# Inverter_Main.net
KiCad netlist of a schematic drawn in Altium Designer
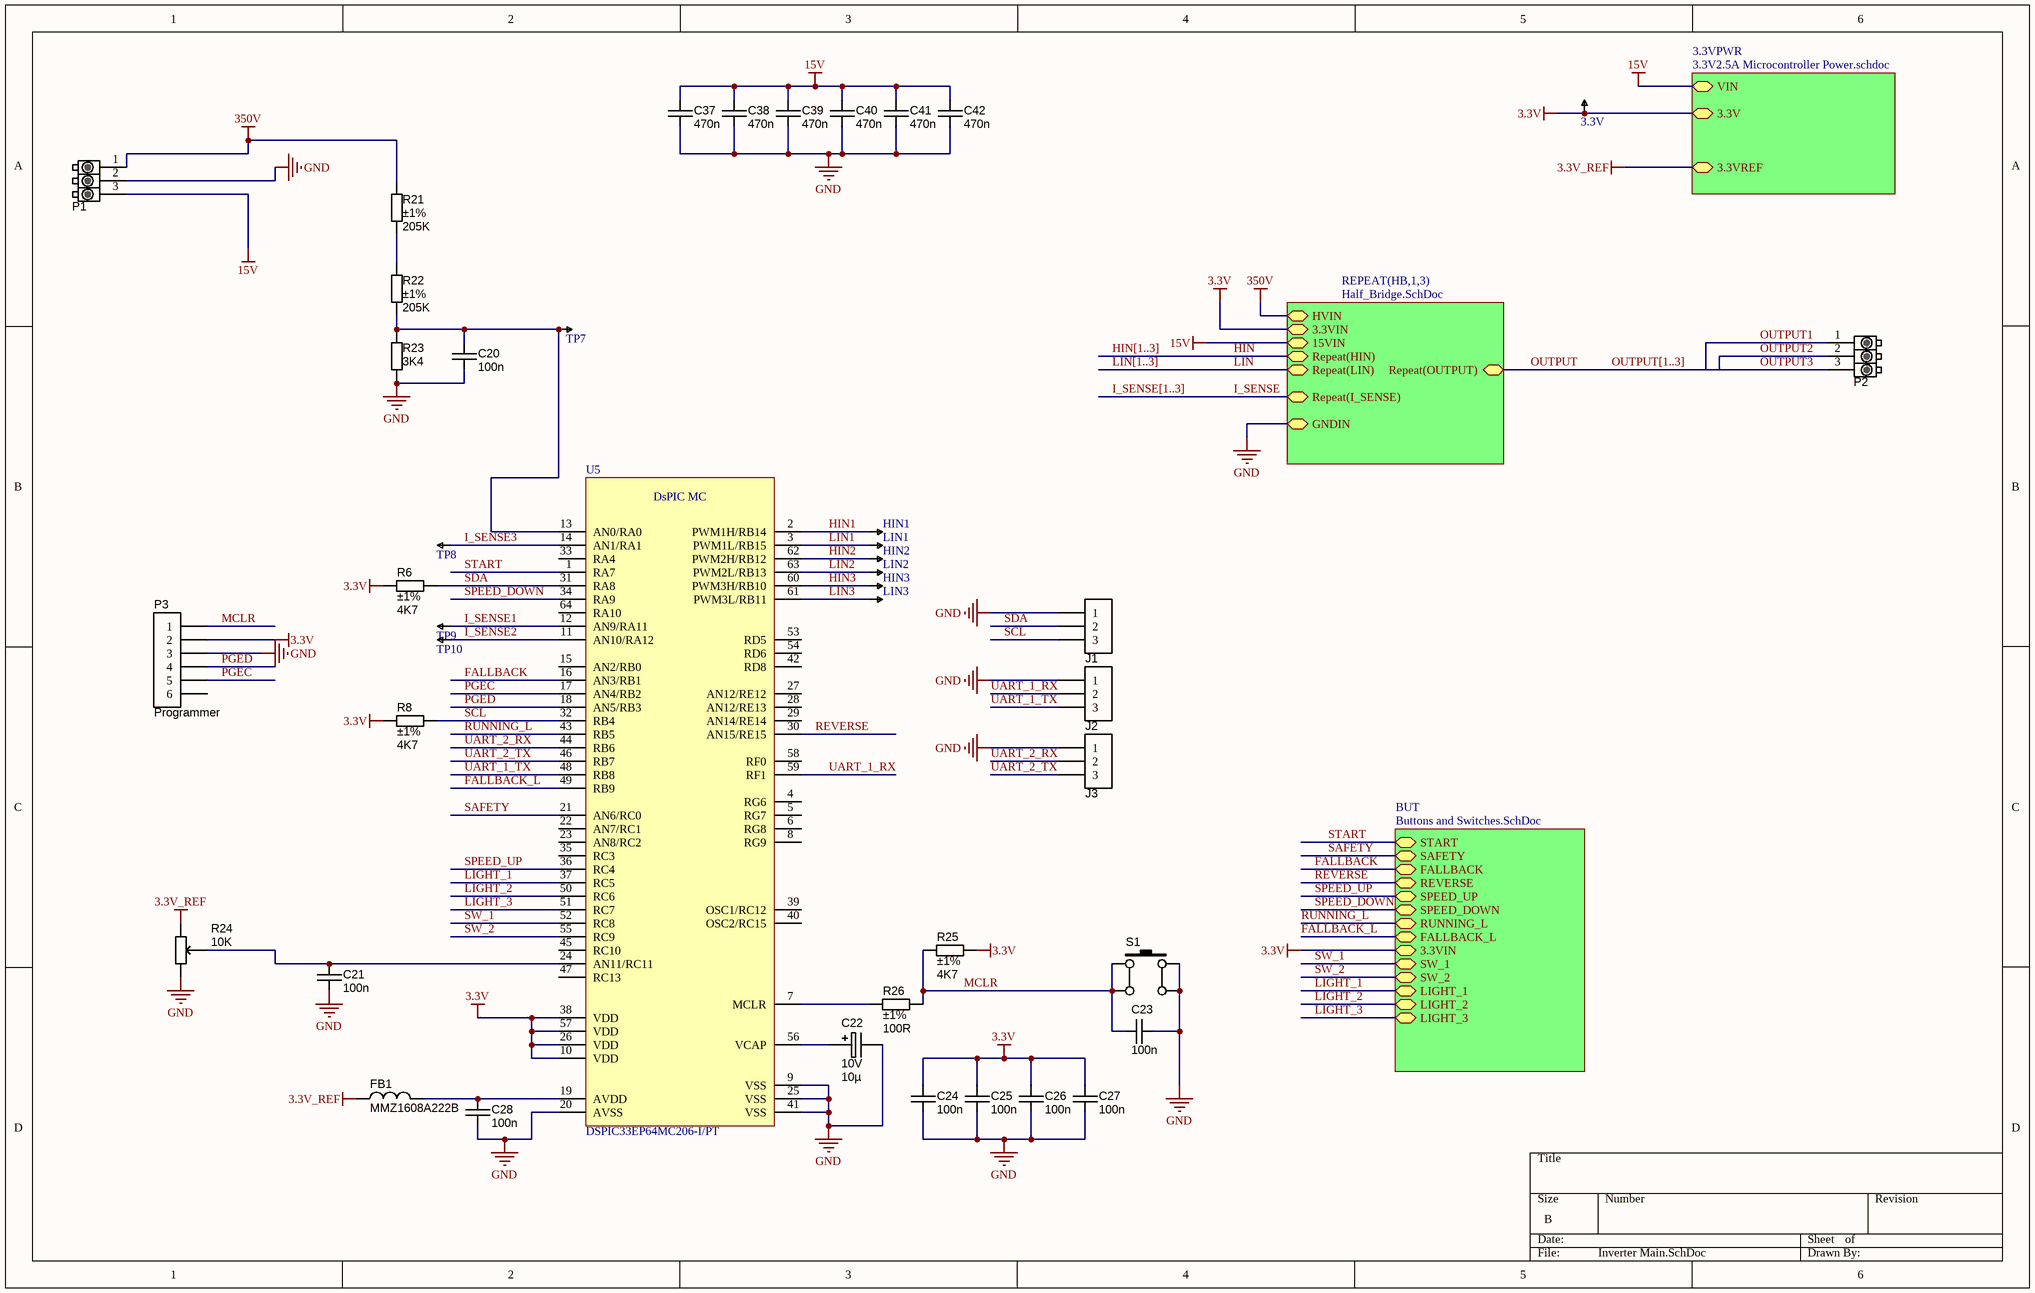
[diagram p0: Inverter Main.SchDoc]

(export (version "E")
  (design (tool "Eeschema 10.0.6"))
  (components
    (comp (ref "3.3V")
      (value "TESTPOINT SMD 1206")
      (footprint "1206 Test Point")
      (fields
        (field (name "MANUFACTURER") "TE Connectivity AMP Connectors")
        (field (name "MANUFACTURER PART NUMBER") "RCS-0C")
      )
      (libsource (lib "PBL - Test Points") (part "TESTPOINT SMD 1206"))
    )
    (comp (ref "C20")
      (value "100n")
      (footprint "CAPC1608X90N")
      (description "Capacitor SMD Cer 100nF 10% 50V X7R 0603")
      (fields
        (field (name "TOLERANCE") "±10%")
        (field (name "MANUFACTURER") "Murata Electronics North America")
      )
      (libsource (lib "PBL - Capacitors") (part "CAPC_100n_0603_X7R_50V_10%"))
    )
    (comp (ref "C21")
      (value "100n")
      (footprint "CAPC1608X90N")
      (description "Capacitor SMD Cer 100nF 10% 50V X7R 0603")
      (fields
        (field (name "TOLERANCE") "±10%")
        (field (name "MANUFACTURER") "Murata Electronics North America")
      )
      (libsource (lib "PBL - Capacitors") (part "CAPC_100n_0603_X7R_50V_10%"))
    )
    (comp (ref "C22")
      (value "10µ")
      (footprint "CAPMP2012X150USR")
      (description "Capacitor SMD Tantalum 10uF 20% 10V 0805")
      (fields (field (name "TOLERANCE") "±20%") (field (name "RATINGS") "10V"))
      (libsource (lib "PBL - Capacitors") (part "CAPT_10u_0805_10V"))
    )
    (comp (ref "C23")
      (value "100n")
      (footprint "CAPC1608X90N")
      (description "Capacitor SMD Cer 100nF 10% 50V X7R 0603")
      (fields
        (field (name "TOLERANCE") "±10%")
        (field (name "MANUFACTURER") "Murata Electronics North America")
      )
      (libsource (lib "PBL - Capacitors") (part "CAPC_100n_0603_X7R_50V_10%"))
    )
    (comp (ref "C24")
      (value "100n")
      (footprint "CAPC1608X90N")
      (description "Capacitor SMD Cer 100nF 10% 50V X7R 0603")
      (fields
        (field (name "TOLERANCE") "±10%")
        (field (name "MANUFACTURER") "Murata Electronics North America")
      )
      (libsource (lib "PBL - Capacitors") (part "CAPC_100n_0603_X7R_50V_10%"))
    )
    (comp (ref "C25")
      (value "100n")
      (footprint "CAPC1608X90N")
      (description "Capacitor SMD Cer 100nF 10% 50V X7R 0603")
      (fields
        (field (name "TOLERANCE") "±10%")
        (field (name "MANUFACTURER") "Murata Electronics North America")
      )
      (libsource (lib "PBL - Capacitors") (part "CAPC_100n_0603_X7R_50V_10%"))
    )
    (comp (ref "C26")
      (value "100n")
      (footprint "CAPC1608X90N")
      (description "Capacitor SMD Cer 100nF 10% 50V X7R 0603")
      (fields
        (field (name "TOLERANCE") "±10%")
        (field (name "MANUFACTURER") "Murata Electronics North America")
      )
      (libsource (lib "PBL - Capacitors") (part "CAPC_100n_0603_X7R_50V_10%"))
    )
    (comp (ref "C27")
      (value "100n")
      (footprint "CAPC1608X90N")
      (description "Capacitor SMD Cer 100nF 10% 50V X7R 0603")
      (fields
        (field (name "TOLERANCE") "±10%")
        (field (name "MANUFACTURER") "Murata Electronics North America")
      )
      (libsource (lib "PBL - Capacitors") (part "CAPC_100n_0603_X7R_50V_10%"))
    )
    (comp (ref "C28")
      (value "100n")
      (footprint "CAPC1608X90N")
      (description "Capacitor SMD Cer 100nF 10% 50V X7R 0603")
      (fields
        (field (name "TOLERANCE") "±10%")
        (field (name "MANUFACTURER") "Murata Electronics North America")
      )
      (libsource (lib "PBL - Capacitors") (part "CAPC_100n_0603_X7R_50V_10%"))
    )
    (comp (ref "C37")
      (value "470n")
      (footprint "CAPC2012X135N")
      (description "0.47µF ±10% 50V Ceramic Capacitor X7R 0805 (2012 Metric)")
      (fields
        (field (name "MANUFACTURER") "Murata Electronics North America")
        (field (name "TOLERANCE") "±10%")
      )
      (libsource (lib "PBL - Capacitors") (part "CAPC_470n_0805_X7R_50V_10%"))
    )
    (comp (ref "C38")
      (value "470n")
      (footprint "CAPC2012X135N")
      (description "0.47µF ±10% 50V Ceramic Capacitor X7R 0805 (2012 Metric)")
      (fields
        (field (name "MANUFACTURER") "Murata Electronics North America")
        (field (name "TOLERANCE") "±10%")
      )
      (libsource (lib "PBL - Capacitors") (part "CAPC_470n_0805_X7R_50V_10%"))
    )
    (comp (ref "C39")
      (value "470n")
      (footprint "CAPC2012X135N")
      (description "0.47µF ±10% 50V Ceramic Capacitor X7R 0805 (2012 Metric)")
      (fields
        (field (name "MANUFACTURER") "Murata Electronics North America")
        (field (name "TOLERANCE") "±10%")
      )
      (libsource (lib "PBL - Capacitors") (part "CAPC_470n_0805_X7R_50V_10%"))
    )
    (comp (ref "C40")
      (value "470n")
      (footprint "CAPC2012X135N")
      (description "0.47µF ±10% 50V Ceramic Capacitor X7R 0805 (2012 Metric)")
      (fields
        (field (name "MANUFACTURER") "Murata Electronics North America")
        (field (name "TOLERANCE") "±10%")
      )
      (libsource (lib "PBL - Capacitors") (part "CAPC_470n_0805_X7R_50V_10%"))
    )
    (comp (ref "C41")
      (value "470n")
      (footprint "CAPC2012X135N")
      (description "0.47µF ±10% 50V Ceramic Capacitor X7R 0805 (2012 Metric)")
      (fields
        (field (name "MANUFACTURER") "Murata Electronics North America")
        (field (name "TOLERANCE") "±10%")
      )
      (libsource (lib "PBL - Capacitors") (part "CAPC_470n_0805_X7R_50V_10%"))
    )
    (comp (ref "C42")
      (value "470n")
      (footprint "CAPC2012X135N")
      (description "0.47µF ±10% 50V Ceramic Capacitor X7R 0805 (2012 Metric)")
      (fields
        (field (name "MANUFACTURER") "Murata Electronics North America")
        (field (name "TOLERANCE") "±10%")
      )
      (libsource (lib "PBL - Capacitors") (part "CAPC_470n_0805_X7R_50V_10%"))
    )
    (comp (ref "FB1")
      (value "2K2 @ 100 MHz")
      (footprint "FBC1608X95N")
      (description "Ferrite bead 2.2K Ohm at 100 MHz 200mA 0603 SMD")
      (fields (field (name "MANUFACTURER PART NUMBER 1") "MMZ1608A222B"))
      (libsource (lib "PBL - Inductors") (part "FERRITE_2K2-100MHz_0603"))
    )
    (comp (ref "HIN1")
      (value "TESTPOINT SMD 1206")
      (footprint "1206 Test Point")
      (fields
        (field (name "MANUFACTURER") "TE Connectivity AMP Connectors")
        (field (name "MANUFACTURER PART NUMBER") "RCS-0C")
      )
      (libsource (lib "PBL - Test Points") (part "TESTPOINT SMD 1206"))
    )
    (comp (ref "HIN2")
      (value "TESTPOINT SMD 1206")
      (footprint "1206 Test Point")
      (fields
        (field (name "MANUFACTURER") "TE Connectivity AMP Connectors")
        (field (name "MANUFACTURER PART NUMBER") "RCS-0C")
      )
      (libsource (lib "PBL - Test Points") (part "TESTPOINT SMD 1206"))
    )
    (comp (ref "HIN3")
      (value "TESTPOINT SMD 1206")
      (footprint "1206 Test Point")
      (fields
        (field (name "MANUFACTURER") "TE Connectivity AMP Connectors")
        (field (name "MANUFACTURER PART NUMBER") "RCS-0C")
      )
      (libsource (lib "PBL - Test Points") (part "TESTPOINT SMD 1206"))
    )
    (comp (ref "J1")
      (value "JST_PH_B3B")
      (footprint "JST_PH_3_B3B")
      (description "2mm Pitch")
      (libsource (lib "PBL - Connectors") (part "JST_PH_B3B"))
    )
    (comp (ref "J2")
      (value "JST_PH_B3B")
      (footprint "JST_PH_3_B3B")
      (description "2mm Pitch")
      (libsource (lib "PBL - Connectors") (part "JST_PH_B3B"))
    )
    (comp (ref "J3")
      (value "JST_PH_B3B")
      (footprint "JST_PH_3_B3B")
      (description "2mm Pitch")
      (libsource (lib "PBL - Connectors") (part "JST_PH_B3B"))
    )
    (comp (ref "LIN1")
      (value "TESTPOINT SMD 1206")
      (footprint "1206 Test Point")
      (fields
        (field (name "MANUFACTURER") "TE Connectivity AMP Connectors")
        (field (name "MANUFACTURER PART NUMBER") "RCS-0C")
      )
      (libsource (lib "PBL - Test Points") (part "TESTPOINT SMD 1206"))
    )
    (comp (ref "LIN2")
      (value "TESTPOINT SMD 1206")
      (footprint "1206 Test Point")
      (fields
        (field (name "MANUFACTURER") "TE Connectivity AMP Connectors")
        (field (name "MANUFACTURER PART NUMBER") "RCS-0C")
      )
      (libsource (lib "PBL - Test Points") (part "TESTPOINT SMD 1206"))
    )
    (comp (ref "LIN3")
      (value "TESTPOINT SMD 1206")
      (footprint "1206 Test Point")
      (fields
        (field (name "MANUFACTURER") "TE Connectivity AMP Connectors")
        (field (name "MANUFACTURER PART NUMBER") "RCS-0C")
      )
      (libsource (lib "PBL - Test Points") (part "TESTPOINT SMD 1206"))
    )
    (comp (ref "P1")
      (value "3P_TERM BLOCK 796739-3")
      (footprint "TE 796739-3 3 Screw Terminal")
      (description "3 Position Wire to Board Terminal Block Horizontal with Board 0.375\" (9.53mm) Through Hole")
      (fields (field (name "MANUFACTURER") "TE Connectivity AMP Connectors") (field (name "VOLTAGE") "600V"))
      (libsource (lib "PBL - Connectors") (part "3P_TERM BLOCK 796739-3"))
    )
    (comp (ref "P2")
      (value "3P_TERM BLOCK 796739-3")
      (footprint "TE 796739-3 3 Screw Terminal")
      (description "3 Position Wire to Board Terminal Block Horizontal with Board 0.375\" (9.53mm) Through Hole")
      (fields (field (name "MANUFACTURER") "TE Connectivity AMP Connectors") (field (name "VOLTAGE") "600V"))
      (libsource (lib "") (part "3P_TERM BLOCK 796739-3_1"))
    )
    (comp (ref "P3")
      (value "Programmer")
      (footprint "HDR1X6")
      (description "Header, 6-pin")
      (libsource (lib "PBL - Connectors") (part "Header6P"))
    )
    (comp (ref "R6")
      (value "4K7")
      (footprint "RESC1608X55N")
      (description "Resistor SMD chip 4.7K Ohm 0.1W 1% 0603")
      (fields
        (field (name "MANUFACTURER") "Yageo")
        (field (name "MANUFACTURER PART NUMBER") "RC0603FR-074K7L")
        (field (name "TOLERANCE") "±1%")
      )
      (libsource (lib "PBL - Resistors") (part "RES_4K7_0603_1%"))
    )
    (comp (ref "R8")
      (value "4K7")
      (footprint "RESC1608X55N")
      (description "Resistor SMD chip 4.7K Ohm 0.1W 1% 0603")
      (fields
        (field (name "MANUFACTURER") "Yageo")
        (field (name "MANUFACTURER PART NUMBER") "RC0603FR-074K7L")
        (field (name "TOLERANCE") "±1%")
      )
      (libsource (lib "PBL - Resistors") (part "RES_4K7_0603_1%"))
    )
    (comp (ref "R21")
      (value "205K")
      (footprint "RESC2012X70N")
      (description "Resistor SMD chip 205k Ohm 0.125W 1% 0805")
      (fields (field (name "TOLERANCE") "±1%") (field (name "Comment") "Thick Film"))
      (libsource (lib "PBL - Resistors") (part "RES_205K_0805_1%"))
    )
    (comp (ref "R22")
      (value "205K")
      (footprint "RESC2012X70N")
      (description "Resistor SMD chip 205k Ohm 0.125W 1% 0805")
      (fields (field (name "TOLERANCE") "±1%") (field (name "Comment") "Thick Film"))
      (libsource (lib "PBL - Resistors") (part "RES_205K_0805_1%"))
    )
    (comp (ref "R23")
      (value "3K4")
      (footprint "RESC1608X55N")
      (description "Resistor SMD chip 3.4k Ohm 0.1W 1% 0603")
      (fields
        (field (name "TOLERANCE") "±1%")
        (field (name "MANUFACTURER") "Panasonic Electronic Components")
      )
      (libsource (lib "PBL - Resistors") (part "RES_3K4_0603_1%"))
    )
    (comp (ref "R24")
      (value "10K")
      (footprint "POT_PDB12_BOURNS")
      (description "10k Ohm 1 Gang Linear Through Hole Potentiometer None 1 Turn Carbon 0.08W PC Pins, Board Locks")
      (fields (field (name "MANUFACTURER") "Bourns Inc.") (field (name "TOLERANCE") "±20%"))
      (libsource (lib "PBL - Resistors") (part "RES_POT_10K_THT_PDB12-H4251-103BF"))
    )
    (comp (ref "R25")
      (value "4K7")
      (footprint "RESC1608X55N")
      (description "Resistor SMD chip 4.7K Ohm 0.1W 1% 0603")
      (fields
        (field (name "MANUFACTURER") "Yageo")
        (field (name "MANUFACTURER PART NUMBER") "RC0603FR-074K7L")
        (field (name "TOLERANCE") "±1%")
      )
      (libsource (lib "PBL - Resistors") (part "RES_4K7_0603_1%"))
    )
    (comp (ref "R26")
      (value "100R")
      (footprint "RESC1608X55N")
      (description "Resistor SMD chip 100 Ohm 0.1W 1% 0603")
      (fields (field (name "TOLERANCE") "±1%") (field (name "Comment") "Thick Film"))
      (libsource (lib "PBL - Resistors") (part "RES_100R_0603_1%"))
    )
    (comp (ref "S1")
      (value "TL3301AF160QJ")
      (footprint "SWITCH_TACT_JLEAD_6mm")
      (description "TACT_SWITCH 6x6 Jlead TL3301AF160QJ")
      (fields (field (name "MANUFACTURER") "E-Switch"))
      (libsource (lib "PBL - Switches") (part "TACT_SWITCH 6x6 JLEAD TL3301AF160QJ"))
    )
    (comp (ref "TP7")
      (value "TESTPOINT SMD 1206")
      (footprint "1206 Test Point")
      (fields
        (field (name "MANUFACTURER") "TE Connectivity AMP Connectors")
        (field (name "MANUFACTURER PART NUMBER") "RCS-0C")
      )
      (libsource (lib "PBL - Test Points") (part "TESTPOINT SMD 1206"))
    )
    (comp (ref "TP8")
      (value "TESTPOINT SMD 1206")
      (footprint "1206 Test Point")
      (fields
        (field (name "MANUFACTURER") "TE Connectivity AMP Connectors")
        (field (name "MANUFACTURER PART NUMBER") "RCS-0C")
      )
      (libsource (lib "PBL - Test Points") (part "TESTPOINT SMD 1206"))
    )
    (comp (ref "TP9")
      (value "TESTPOINT SMD 1206")
      (footprint "1206 Test Point")
      (fields
        (field (name "MANUFACTURER") "TE Connectivity AMP Connectors")
        (field (name "MANUFACTURER PART NUMBER") "RCS-0C")
      )
      (libsource (lib "PBL - Test Points") (part "TESTPOINT SMD 1206"))
    )
    (comp (ref "TP10")
      (value "TESTPOINT SMD 1206")
      (footprint "1206 Test Point")
      (fields
        (field (name "MANUFACTURER") "TE Connectivity AMP Connectors")
        (field (name "MANUFACTURER PART NUMBER") "RCS-0C")
      )
      (libsource (lib "PBL - Test Points") (part "TESTPOINT SMD 1206"))
    )
    (comp (ref "U5")
      (value "uC_dsPIC33EP64MC206")
      (footprint "LQFP50P1200X1200X160-64")
      (description "DSPIC33EP64MC206-I/PT")
      (fields
        (field (name "MANUFACTURER") "Microchip Technology")
        (field (name "MANUFACTURER PART NUMBER") "DSPIC33EP64MC206-I/PT")
      )
      (libsource (lib "PBL - Integrated Circuits") (part "uC_dsPIC33EP64MC206"))
    )
  )
  (nets
    (net (code "1") (name "/FALLBACK") (class "Default")
      (node (ref "U5") (pin "16") (pinfunction "AN3/RB1_16") (pintype "passive"))
    )
    (net (code "2") (name "/FALLBACK_L") (class "Default")
      (node (ref "U5") (pin "49") (pinfunction "RB9_49") (pintype "passive"))
    )
    (net (code "4") (name "/HIN1") (class "Default")
      (node (ref "HIN1") (pin "1") (pintype "passive"))
      (node (ref "U5") (pin "2") (pinfunction "PWM1H/RB14_2") (pintype "passive"))
    )
    (net (code "5") (name "/HIN2") (class "Default")
      (node (ref "HIN2") (pin "1") (pintype "passive"))
      (node (ref "U5") (pin "62") (pinfunction "PWM2H/RB12_62") (pintype "passive"))
    )
    (net (code "6") (name "/HIN3") (class "Default")
      (node (ref "HIN3") (pin "1") (pintype "passive"))
      (node (ref "U5") (pin "60") (pinfunction "PWM3H/RB10_60") (pintype "passive"))
    )
    (net (code "9") (name "/I_SENSE1") (class "Default")
      (node (ref "TP9") (pin "1") (pintype "passive"))
      (node (ref "U5") (pin "12") (pinfunction "AN9/RA11_12") (pintype "passive"))
    )
    (net (code "10") (name "/I_SENSE2") (class "Default")
      (node (ref "TP10") (pin "1") (pintype "passive"))
      (node (ref "U5") (pin "11") (pinfunction "AN10/RA12_11") (pintype "passive"))
    )
    (net (code "11") (name "/I_SENSE3") (class "Default")
      (node (ref "TP8") (pin "1") (pintype "passive"))
      (node (ref "U5") (pin "14") (pinfunction "AN1/RA1_14") (pintype "passive"))
    )
    (net (code "13") (name "/LIGHT_1") (class "Default")
      (node (ref "U5") (pin "37") (pinfunction "RC5_37") (pintype "passive"))
    )
    (net (code "14") (name "/LIGHT_2") (class "Default")
      (node (ref "U5") (pin "50") (pinfunction "RC6_50") (pintype "passive"))
    )
    (net (code "15") (name "/LIGHT_3") (class "Default")
      (node (ref "U5") (pin "51") (pinfunction "RC7_51") (pintype "passive"))
    )
    (net (code "17") (name "/LIN1") (class "Default")
      (node (ref "LIN1") (pin "1") (pintype "passive"))
      (node (ref "U5") (pin "3") (pinfunction "PWM1L/RB15_3") (pintype "passive"))
    )
    (net (code "18") (name "/LIN2") (class "Default")
      (node (ref "LIN2") (pin "1") (pintype "passive"))
      (node (ref "U5") (pin "63") (pinfunction "PWM2L/RB13_63") (pintype "passive"))
    )
    (net (code "19") (name "/LIN3") (class "Default")
      (node (ref "LIN3") (pin "1") (pintype "passive"))
      (node (ref "U5") (pin "61") (pinfunction "PWM3L/RB11_61") (pintype "passive"))
    )
    (net (code "21") (name "/MCLR") (class "Default")
      (node (ref "C23") (pin "1") (pintype "passive"))
      (node (ref "P3") (pin "1") (pinfunction "1_1") (pintype "passive"))
      (node (ref "R25") (pin "1") (pinfunction "1_1") (pintype "passive"))
      (node (ref "R26") (pin "2") (pinfunction "2_2") (pintype "passive"))
      (node (ref "S1") (pin "1") (pintype "passive"))
      (node (ref "S1") (pin "2") (pintype "passive"))
    )
    (net (code "23") (name "/OUTPUT1") (class "Default")
      (node (ref "P2") (pin "1") (pinfunction "1_1") (pintype "passive"))
    )
    (net (code "24") (name "/OUTPUT2") (class "Default")
      (node (ref "P2") (pin "2") (pinfunction "2_2") (pintype "passive"))
    )
    (net (code "25") (name "/OUTPUT3") (class "Default")
      (node (ref "P2") (pin "3") (pinfunction "3_3") (pintype "passive"))
    )
    (net (code "27") (name "/PGEC") (class "Default")
      (node (ref "P3") (pin "5") (pinfunction "5_5") (pintype "passive"))
      (node (ref "U5") (pin "17") (pinfunction "AN4/RB2_17") (pintype "passive"))
    )
    (net (code "28") (name "/PGED") (class "Default")
      (node (ref "P3") (pin "4") (pinfunction "4_4") (pintype "passive"))
      (node (ref "U5") (pin "18") (pinfunction "AN5/RB3_18") (pintype "passive"))
    )
    (net (code "29") (name "/REVERSE") (class "Default")
      (node (ref "U5") (pin "30") (pinfunction "AN15/RE15_30") (pintype "passive"))
    )
    (net (code "30") (name "/RUNNING_L") (class "Default")
      (node (ref "U5") (pin "43") (pinfunction "RB5_43") (pintype "passive"))
    )
    (net (code "31") (name "/SAFETY") (class "Default")
      (node (ref "U5") (pin "21") (pinfunction "AN6/RC0_21") (pintype "passive"))
    )
    (net (code "32") (name "/SCL") (class "Default")
      (node (ref "J1") (pin "3") (pinfunction "3_3") (pintype "passive"))
      (node (ref "R8") (pin "2") (pinfunction "2_2") (pintype "passive"))
      (node (ref "U5") (pin "32") (pinfunction "RB4_32") (pintype "passive"))
    )
    (net (code "33") (name "/SDA") (class "Default")
      (node (ref "J1") (pin "2") (pinfunction "2_2") (pintype "passive"))
      (node (ref "R6") (pin "2") (pinfunction "2_2") (pintype "passive"))
      (node (ref "U5") (pin "31") (pinfunction "RA8_31") (pintype "passive"))
    )
    (net (code "34") (name "/SPEED_DOWN") (class "Default")
      (node (ref "U5") (pin "34") (pinfunction "RA9_34") (pintype "passive"))
    )
    (net (code "35") (name "/SPEED_UP") (class "Default")
      (node (ref "U5") (pin "36") (pinfunction "RC4_36") (pintype "passive"))
    )
    (net (code "36") (name "/START") (class "Default")
      (node (ref "U5") (pin "1") (pinfunction "RA7_1") (pintype "passive"))
    )
    (net (code "37") (name "/SW_1") (class "Default")
      (node (ref "U5") (pin "52") (pinfunction "RC8_52") (pintype "passive"))
    )
    (net (code "38") (name "/SW_2") (class "Default")
      (node (ref "U5") (pin "55") (pinfunction "RC9_55") (pintype "passive"))
    )
    (net (code "39") (name "/UART_1_RX") (class "Default")
      (node (ref "J2") (pin "2") (pinfunction "2_2") (pintype "passive"))
      (node (ref "U5") (pin "59") (pinfunction "RF1_59") (pintype "passive"))
    )
    (net (code "40") (name "/UART_1_TX") (class "Default")
      (node (ref "J2") (pin "3") (pinfunction "3_3") (pintype "passive"))
      (node (ref "U5") (pin "48") (pinfunction "RB8_48") (pintype "passive"))
    )
    (net (code "41") (name "/UART_2_RX") (class "Default")
      (node (ref "J3") (pin "2") (pinfunction "2_2") (pintype "passive"))
      (node (ref "U5") (pin "44") (pinfunction "RB6_44") (pintype "passive"))
    )
    (net (code "42") (name "/UART_2_TX") (class "Default")
      (node (ref "J3") (pin "3") (pinfunction "3_3") (pintype "passive"))
      (node (ref "U5") (pin "46") (pinfunction "RB7_46") (pintype "passive"))
    )
    (net (code "43") (name "3.3V") (class "Default")
      (node (ref "3.3V") (pin "1") (pintype "passive"))
      (node (ref "C24") (pin "1") (pintype "passive"))
      (node (ref "C25") (pin "1") (pintype "passive"))
      (node (ref "C26") (pin "1") (pintype "passive"))
      (node (ref "C27") (pin "1") (pintype "passive"))
      (node (ref "P3") (pin "2") (pinfunction "2_2") (pintype "passive"))
      (node (ref "R25") (pin "2") (pinfunction "2_2") (pintype "passive"))
      (node (ref "R6") (pin "1") (pinfunction "1_1") (pintype "passive"))
      (node (ref "R8") (pin "1") (pinfunction "1_1") (pintype "passive"))
      (node (ref "U5") (pin "10") (pinfunction "VDD_10") (pintype "passive"))
      (node (ref "U5") (pin "26") (pinfunction "VDD_26") (pintype "passive"))
      (node (ref "U5") (pin "38") (pinfunction "VDD_38") (pintype "passive"))
      (node (ref "U5") (pin "57") (pinfunction "VDD_57") (pintype "passive"))
    )
    (net (code "44") (name "3.3V_REF") (class "Default")
      (node (ref "FB1") (pin "1") (pinfunction "1_1") (pintype "passive"))
      (node (ref "R24") (pin "1") (pinfunction "3_1") (pintype "passive"))
    )
    (net (code "45") (name "15V") (class "Default")
      (node (ref "C37") (pin "1") (pintype "passive"))
      (node (ref "C38") (pin "1") (pintype "passive"))
      (node (ref "C39") (pin "1") (pintype "passive"))
      (node (ref "C40") (pin "1") (pintype "passive"))
      (node (ref "C41") (pin "1") (pintype "passive"))
      (node (ref "C42") (pin "1") (pintype "passive"))
      (node (ref "P1") (pin "3") (pinfunction "3_3") (pintype "passive"))
    )
    (net (code "46") (name "350V") (class "Default")
      (node (ref "P1") (pin "1") (pinfunction "1_1") (pintype "passive"))
      (node (ref "R21") (pin "1") (pinfunction "1_1") (pintype "passive"))
    )
    (net (code "47") (name "GND") (class "Default")
      (node (ref "C20") (pin "2") (pintype "passive"))
      (node (ref "C21") (pin "2") (pintype "passive"))
      (node (ref "C22") (pin "2") (pintype "passive"))
      (node (ref "C23") (pin "2") (pintype "passive"))
      (node (ref "C24") (pin "2") (pintype "passive"))
      (node (ref "C25") (pin "2") (pintype "passive"))
      (node (ref "C26") (pin "2") (pintype "passive"))
      (node (ref "C27") (pin "2") (pintype "passive"))
      (node (ref "C28") (pin "2") (pintype "passive"))
      (node (ref "C37") (pin "2") (pintype "passive"))
      (node (ref "C38") (pin "2") (pintype "passive"))
      (node (ref "C39") (pin "2") (pintype "passive"))
      (node (ref "C40") (pin "2") (pintype "passive"))
      (node (ref "C41") (pin "2") (pintype "passive"))
      (node (ref "C42") (pin "2") (pintype "passive"))
      (node (ref "J1") (pin "1") (pinfunction "1_1") (pintype "passive"))
      (node (ref "J2") (pin "1") (pinfunction "1_1") (pintype "passive"))
      (node (ref "J3") (pin "1") (pinfunction "1_1") (pintype "passive"))
      (node (ref "P1") (pin "2") (pinfunction "2_2") (pintype "passive"))
      (node (ref "P3") (pin "3") (pinfunction "3_3") (pintype "passive"))
      (node (ref "R23") (pin "2") (pinfunction "2_2") (pintype "passive"))
      (node (ref "R24") (pin "3") (pinfunction "1_3") (pintype "passive"))
      (node (ref "S1") (pin "3") (pintype "passive"))
      (node (ref "S1") (pin "4") (pintype "passive"))
      (node (ref "U5") (pin "20") (pinfunction "AVSS_20") (pintype "passive"))
      (node (ref "U5") (pin "25") (pinfunction "VSS_25") (pintype "passive"))
      (node (ref "U5") (pin "41") (pinfunction "VSS_41") (pintype "passive"))
      (node (ref "U5") (pin "9") (pinfunction "VSS_9") (pintype "passive"))
    )
    (net (code "48") (name "Net-(R21-Pad2)") (class "Default")
      (node (ref "R21") (pin "2") (pinfunction "2_2") (pintype "passive"))
      (node (ref "R22") (pin "1") (pinfunction "1_1") (pintype "passive"))
    )
    (net (code "49") (name "Net-(U5-AN0{slash}RA0)") (class "Default")
      (node (ref "C20") (pin "1") (pintype "passive"))
      (node (ref "R22") (pin "2") (pinfunction "2_2") (pintype "passive"))
      (node (ref "R23") (pin "1") (pinfunction "1_1") (pintype "passive"))
      (node (ref "TP7") (pin "1") (pintype "passive"))
      (node (ref "U5") (pin "13") (pinfunction "AN0/RA0_13") (pintype "passive"))
    )
    (net (code "50") (name "Net-(U5-AN11{slash}RC11)") (class "Default")
      (node (ref "C21") (pin "1") (pintype "passive"))
      (node (ref "R24") (pin "2") (pinfunction "2_2") (pintype "passive"))
      (node (ref "U5") (pin "24") (pinfunction "AN11/RC11_24") (pintype "passive"))
    )
    (net (code "51") (name "Net-(U5-AVDD)") (class "Default")
      (node (ref "C28") (pin "1") (pintype "passive"))
      (node (ref "FB1") (pin "2") (pinfunction "2_2") (pintype "passive"))
      (node (ref "U5") (pin "19") (pinfunction "AVDD_19") (pintype "passive"))
    )
    (net (code "52") (name "Net-(U5-MCLR)") (class "Default")
      (node (ref "R26") (pin "1") (pinfunction "1_1") (pintype "passive"))
      (node (ref "U5") (pin "7") (pinfunction "MCLR_7") (pintype "passive"))
    )
    (net (code "53") (name "Net-(U5-VCAP)") (class "Default")
      (node (ref "C22") (pin "1") (pintype "passive"))
      (node (ref "U5") (pin "56") (pinfunction "VCAP_56") (pintype "passive"))
    )
    (net (code "54") (name "unconnected-(P3-Pad6)") (class "Default")
      (node (ref "P3") (pin "6") (pinfunction "6_6") (pintype "passive"))
    )
    (net (code "55") (name "unconnected-(U5-AN2{slash}RB0-Pad15)") (class "Default")
      (node (ref "U5") (pin "15") (pinfunction "AN2/RB0_15") (pintype "passive"))
    )
    (net (code "56") (name "unconnected-(U5-AN7{slash}RC1-Pad22)") (class "Default")
      (node (ref "U5") (pin "22") (pinfunction "AN7/RC1_22") (pintype "passive"))
    )
    (net (code "57") (name "unconnected-(U5-AN8{slash}RC2-Pad23)") (class "Default")
      (node (ref "U5") (pin "23") (pinfunction "AN8/RC2_23") (pintype "passive"))
    )
    (net (code "58") (name "unconnected-(U5-AN12{slash}RE12-Pad27)") (class "Default")
      (node (ref "U5") (pin "27") (pinfunction "AN12/RE12_27") (pintype "passive"))
    )
    (net (code "59") (name "unconnected-(U5-AN12{slash}RE13-Pad28)") (class "Default")
      (node (ref "U5") (pin "28") (pinfunction "AN12/RE13_28") (pintype "passive"))
    )
    (net (code "60") (name "unconnected-(U5-AN14{slash}RE14-Pad29)") (class "Default")
      (node (ref "U5") (pin "29") (pinfunction "AN14/RE14_29") (pintype "passive"))
    )
    (net (code "61") (name "unconnected-(U5-OSC1{slash}RC12-Pad39)") (class "Default")
      (node (ref "U5") (pin "39") (pinfunction "OSC1/RC12_39") (pintype "passive"))
    )
    (net (code "62") (name "unconnected-(U5-OSC2{slash}RC15-Pad40)") (class "Default")
      (node (ref "U5") (pin "40") (pinfunction "OSC2/RC15_40") (pintype "passive"))
    )
    (net (code "63") (name "unconnected-(U5-RA4-Pad33)") (class "Default")
      (node (ref "U5") (pin "33") (pinfunction "RA4_33") (pintype "passive"))
    )
    (net (code "64") (name "unconnected-(U5-RA10-Pad64)") (class "Default")
      (node (ref "U5") (pin "64") (pinfunction "RA10_64") (pintype "passive"))
    )
    (net (code "65") (name "unconnected-(U5-RC3-Pad35)") (class "Default")
      (node (ref "U5") (pin "35") (pinfunction "RC3_35") (pintype "passive"))
    )
    (net (code "66") (name "unconnected-(U5-RC10-Pad45)") (class "Default")
      (node (ref "U5") (pin "45") (pinfunction "RC10_45") (pintype "passive"))
    )
    (net (code "67") (name "unconnected-(U5-RC13-Pad47)") (class "Default")
      (node (ref "U5") (pin "47") (pinfunction "RC13_47") (pintype "passive"))
    )
    (net (code "68") (name "unconnected-(U5-RD5-Pad53)") (class "Default")
      (node (ref "U5") (pin "53") (pinfunction "RD5_53") (pintype "passive"))
    )
    (net (code "69") (name "unconnected-(U5-RD6-Pad54)") (class "Default")
      (node (ref "U5") (pin "54") (pinfunction "RD6_54") (pintype "passive"))
    )
    (net (code "70") (name "unconnected-(U5-RD8-Pad42)") (class "Default")
      (node (ref "U5") (pin "42") (pinfunction "RD8_42") (pintype "passive"))
    )
    (net (code "71") (name "unconnected-(U5-RF0-Pad58)") (class "Default")
      (node (ref "U5") (pin "58") (pinfunction "RF0_58") (pintype "passive"))
    )
    (net (code "72") (name "unconnected-(U5-RG6-Pad4)") (class "Default")
      (node (ref "U5") (pin "4") (pinfunction "RG6_4") (pintype "passive"))
    )
    (net (code "73") (name "unconnected-(U5-RG7-Pad5)") (class "Default")
      (node (ref "U5") (pin "5") (pinfunction "RG7_5") (pintype "passive"))
    )
    (net (code "74") (name "unconnected-(U5-RG8-Pad6)") (class "Default")
      (node (ref "U5") (pin "6") (pinfunction "RG8_6") (pintype "passive"))
    )
    (net (code "75") (name "unconnected-(U5-RG9-Pad8)") (class "Default")
      (node (ref "U5") (pin "8") (pinfunction "RG9_8") (pintype "passive"))
    )
  )
)
